# altimetr.net
KiCad netlist of a schematic drawn in EAGLE
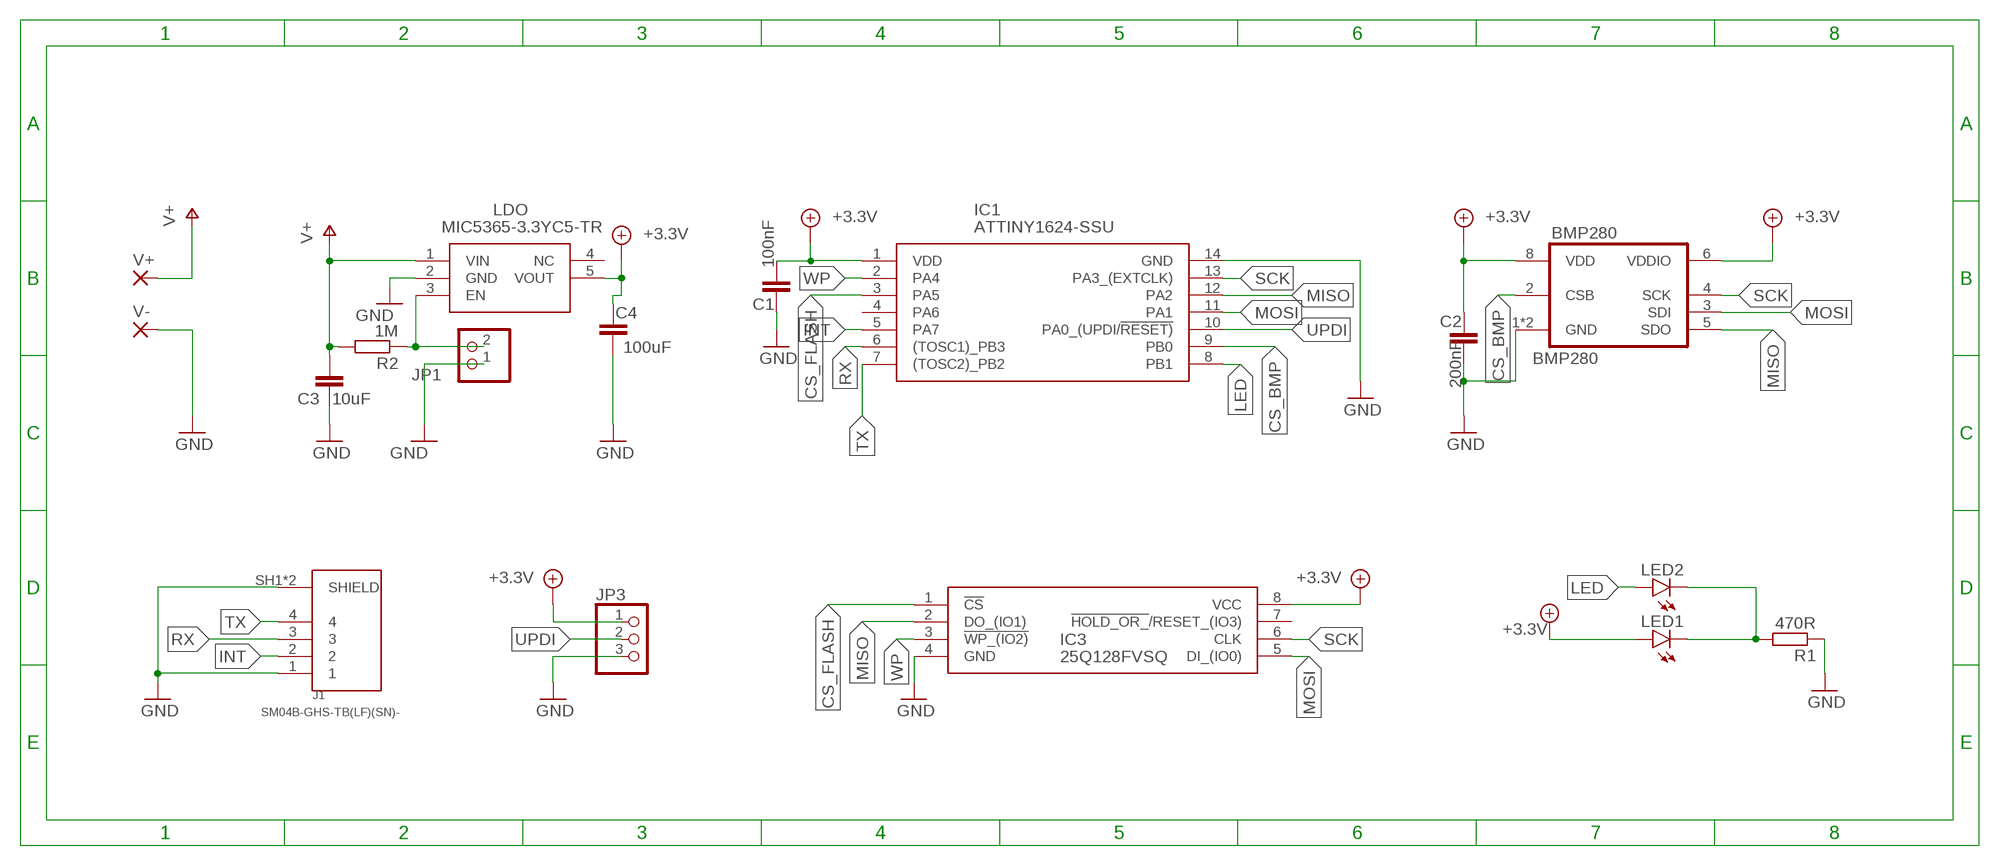
[diagram p0: schematic, sheet 1]

(export (version "E")
  (design (tool "Eeschema 10.0.6"))
  (components
    (comp (ref "BMP280")
      (value "BMP280")
      (footprint "eagle-import:BMP280")
      (libsource (lib "eagle-import") (part "BMP280"))
    )
    (comp (ref "C1")
      (value "100nF")
      (footprint "eagle-import:C0805")
      (libsource (lib "eagle-import") (part "rcl_334_C-EUC0805"))
    )
    (comp (ref "C2")
      (value "200nF")
      (footprint "eagle-import:C0805")
      (libsource (lib "eagle-import") (part "C-EUC0805"))
    )
    (comp (ref "C3")
      (value "10uF")
      (footprint "eagle-import:C0805")
      (libsource (lib "eagle-import") (part "rcl_334_C-EUC0805"))
    )
    (comp (ref "C4")
      (value "100uF")
      (footprint "eagle-import:C0805")
      (libsource (lib "eagle-import") (part "rcl_334_C-EUC0805"))
    )
    (comp (ref "IC1")
      (value "ATTINY1624-SSU")
      (footprint "eagle-import:SOIC127P600X175-14N")
      (fields (field (name "MOUSER_PART_NUMBER") "556-ATTINY1624-SSU"))
      (libsource (lib "eagle-import") (part "ATTINY1624-SSU"))
    )
    (comp (ref "IC3")
      (value "25Q128FVSQ")
      (footprint "eagle-import:SOIC127P790X216-8N")
      (libsource (lib "eagle-import") (part "25Q128FVSQ"))
    )
    (comp (ref "J1")
      (value "SM04B-GHS-TB(LF)(SN)-")
      (footprint "eagle-import:JST_SM04B-GHS-TB(LF)(SN)-")
      (fields (field (name "DIGI-KEY_PART_NUMBER") "455-1566-6-ND") (field (name "MF") "JST Sales"))
      (libsource (lib "eagle-import") (part "SM04B-GHS-TB(LF)(SN)-"))
    )
    (comp (ref "JP1")
      (value "PINHD-1X2/90")
      (footprint "eagle-import:1X02_90")
      (libsource (lib "eagle-import") (part "PINHD-1X2/90"))
    )
    (comp (ref "JP3")
      (value "PINHD-1X3/90")
      (footprint "eagle-import:1X03_90")
      (libsource (lib "eagle-import") (part "PINHD-1X3/90"))
    )
    (comp (ref "LDO")
      (value "MIC5365-3.3YC5-TR")
      (footprint "eagle-import:SOT65P210X110-5N")
      (fields (field (name "MOUSER_PART_NUMBER") "998-MIC5365-3.3YC5TR"))
      (libsource (lib "eagle-import") (part "MIC5365-3.3YC5-TR"))
    )
    (comp (ref "LED1")
      (value "LEDCHIP-LED0805")
      (footprint "eagle-import:CHIP-LED0805")
      (libsource (lib "eagle-import") (part "LEDCHIP-LED0805"))
    )
    (comp (ref "LED2")
      (value "LEDCHIP-LED0805")
      (footprint "eagle-import:CHIP-LED0805")
      (libsource (lib "eagle-import") (part "LEDCHIP-LED0805"))
    )
    (comp (ref "R1")
      (value "470R")
      (footprint "eagle-import:R0805")
      (libsource (lib "eagle-import") (part "rcl_334_R-EU_R0805"))
    )
    (comp (ref "R2")
      (value "1M")
      (footprint "eagle-import:R0805")
      (libsource (lib "eagle-import") (part "R-EU_R0805"))
    )
    (comp (ref "V+")
      (value "SMD2")
      (footprint "eagle-import:SMD1,27-2,54")
      (libsource (lib "eagle-import") (part "SMD2"))
    )
    (comp (ref "V-")
      (value "SMD2")
      (footprint "eagle-import:SMD1,27-2,54")
      (libsource (lib "eagle-import") (part "SMD2"))
    )
  )
  (nets
    (net (code "1") (name "+3.3V") (class "Default")
      (node (ref "BMP280") (pin "6") (pinfunction "VDDIO_6") (pintype "power_in"))
      (node (ref "BMP280") (pin "8") (pinfunction "VDD_8") (pintype "power_in"))
      (node (ref "C1") (pin "1") (pinfunction "1_1") (pintype "passive"))
      (node (ref "C2") (pin "1") (pinfunction "1_1") (pintype "passive"))
      (node (ref "C4") (pin "2") (pinfunction "2_2") (pintype "passive"))
      (node (ref "IC1") (pin "1") (pinfunction "VDD_1") (pintype "bidirectional"))
      (node (ref "IC3") (pin "8") (pinfunction "VCC_8") (pintype "bidirectional"))
      (node (ref "JP3") (pin "1") (pinfunction "1_1") (pintype "passive"))
      (node (ref "LDO") (pin "5") (pinfunction "VOUT_5") (pintype "output"))
      (node (ref "LED1") (pin "A") (pinfunction "A_A") (pintype "passive"))
    )
    (net (code "2") (name "CS_BMP") (class "Default")
      (node (ref "BMP280") (pin "2") (pinfunction "CSB_2") (pintype "input"))
      (node (ref "IC1") (pin "9") (pinfunction "PB0_9") (pintype "bidirectional"))
    )
    (net (code "3") (name "CS_FLASH") (class "Default")
      (node (ref "IC1") (pin "3") (pinfunction "PA5_3") (pintype "bidirectional"))
      (node (ref "IC3") (pin "1") (pinfunction "~{CS}_1") (pintype "bidirectional"))
    )
    (net (code "4") (name "GND") (class "Default")
      (node (ref "BMP280") (pin "1") (pinfunction "GND_1") (pintype "power_in"))
      (node (ref "BMP280") (pin "7") (pinfunction "GND_7") (pintype "power_in"))
      (node (ref "C1") (pin "2") (pinfunction "2_2") (pintype "passive"))
      (node (ref "C2") (pin "2") (pinfunction "2_2") (pintype "passive"))
      (node (ref "C3") (pin "1") (pinfunction "1_1") (pintype "passive"))
      (node (ref "C4") (pin "1") (pinfunction "1_1") (pintype "passive"))
      (node (ref "IC1") (pin "14") (pinfunction "GND_14") (pintype "bidirectional"))
      (node (ref "IC3") (pin "4") (pinfunction "GND_4") (pintype "bidirectional"))
      (node (ref "J1") (pin "1") (pinfunction "1_1") (pintype "passive"))
      (node (ref "J1") (pin "SH1") (pinfunction "SHIELD_SH1") (pintype "power_in"))
      (node (ref "J1") (pin "SH2") (pinfunction "SHIELD_SH2") (pintype "power_in"))
      (node (ref "JP1") (pin "1") (pinfunction "1_1") (pintype "passive"))
      (node (ref "JP3") (pin "3") (pinfunction "3_3") (pintype "passive"))
      (node (ref "LDO") (pin "2") (pinfunction "GND_2") (pintype "power_in"))
      (node (ref "R1") (pin "1") (pinfunction "1_1") (pintype "passive"))
      (node (ref "V-") (pin "1") (pinfunction "P_1") (pintype "passive"))
    )
    (net (code "5") (name "INT") (class "Default")
      (node (ref "IC1") (pin "5") (pinfunction "PA7_5") (pintype "bidirectional"))
      (node (ref "J1") (pin "2") (pinfunction "2_2") (pintype "passive"))
    )
    (net (code "6") (name "LED") (class "Default")
      (node (ref "IC1") (pin "8") (pinfunction "PB1_8") (pintype "bidirectional"))
      (node (ref "LED2") (pin "A") (pinfunction "A_A") (pintype "passive"))
    )
    (net (code "7") (name "MISO") (class "Default")
      (node (ref "BMP280") (pin "5") (pinfunction "SDO_5") (pintype "input"))
      (node (ref "IC1") (pin "12") (pinfunction "PA2_12") (pintype "bidirectional"))
      (node (ref "IC3") (pin "2") (pinfunction "DO_(IO1)_2") (pintype "bidirectional"))
    )
    (net (code "8") (name "MOSI") (class "Default")
      (node (ref "BMP280") (pin "3") (pinfunction "SDI_3") (pintype "bidirectional"))
      (node (ref "IC1") (pin "11") (pinfunction "PA1_11") (pintype "bidirectional"))
      (node (ref "IC3") (pin "5") (pinfunction "DI_(IO0)_5") (pintype "bidirectional"))
    )
    (net (code "9") (name "Net-(LDO-EN)") (class "Default")
      (node (ref "JP1") (pin "2") (pinfunction "2_2") (pintype "passive"))
      (node (ref "LDO") (pin "3") (pinfunction "EN_3") (pintype "input"))
      (node (ref "R2") (pin "1") (pinfunction "1_1") (pintype "passive"))
    )
    (net (code "10") (name "Net-(LED1-PadC)") (class "Default")
      (node (ref "LED1") (pin "C") (pinfunction "C_C") (pintype "passive"))
      (node (ref "LED2") (pin "C") (pinfunction "C_C") (pintype "passive"))
      (node (ref "R1") (pin "2") (pinfunction "2_2") (pintype "passive"))
    )
    (net (code "11") (name "RX") (class "Default")
      (node (ref "IC1") (pin "6") (pinfunction "(TOSC1)_PB3_6") (pintype "bidirectional"))
      (node (ref "J1") (pin "3") (pinfunction "3_3") (pintype "passive"))
    )
    (net (code "12") (name "SCK") (class "Default")
      (node (ref "BMP280") (pin "4") (pinfunction "SCK_4") (pintype "bidirectional"))
      (node (ref "IC1") (pin "13") (pinfunction "PA3_(EXTCLK)_13") (pintype "bidirectional"))
      (node (ref "IC3") (pin "6") (pinfunction "CLK_6") (pintype "bidirectional"))
    )
    (net (code "13") (name "TX") (class "Default")
      (node (ref "IC1") (pin "7") (pinfunction "(TOSC2)_PB2_7") (pintype "bidirectional"))
      (node (ref "J1") (pin "4") (pinfunction "4_4") (pintype "passive"))
    )
    (net (code "14") (name "UPDI") (class "Default")
      (node (ref "IC1") (pin "10") (pinfunction "PA0_(UPDI/~{RESET})_10") (pintype "bidirectional"))
      (node (ref "JP3") (pin "2") (pinfunction "2_2") (pintype "passive"))
    )
    (net (code "15") (name "V+") (class "Default")
      (node (ref "C3") (pin "2") (pinfunction "2_2") (pintype "passive"))
      (node (ref "LDO") (pin "1") (pinfunction "VIN_1") (pintype "power_in"))
      (node (ref "R2") (pin "2") (pinfunction "2_2") (pintype "passive"))
      (node (ref "V+") (pin "1") (pinfunction "P_1") (pintype "passive"))
    )
    (net (code "16") (name "WP") (class "Default")
      (node (ref "IC1") (pin "2") (pinfunction "PA4_2") (pintype "bidirectional"))
      (node (ref "IC3") (pin "3") (pinfunction "~{WP_(IO2})_3") (pintype "bidirectional"))
    )
    (net (code "17") (name "unconnected-(IC1-PA6-Pad4)") (class "Default")
      (node (ref "IC1") (pin "4") (pinfunction "PA6_4") (pintype "bidirectional"))
    )
    (net (code "18") (name "unconnected-(IC3-~{HOLD_OR_}{slash}RESET_(IO3)-Pad7)") (class "Default")
      (node (ref "IC3") (pin "7") (pinfunction "~{HOLD_OR_}/RESET_(IO3)_7") (pintype "bidirectional"))
    )
    (net (code "19") (name "unconnected-(LDO-NC-Pad4)") (class "Default")
      (node (ref "LDO") (pin "4") (pinfunction "NC_4") (pintype "no_connect"))
    )
  )
)
